# final_revision.net
KiCad netlist of a schematic drawn in EAGLE
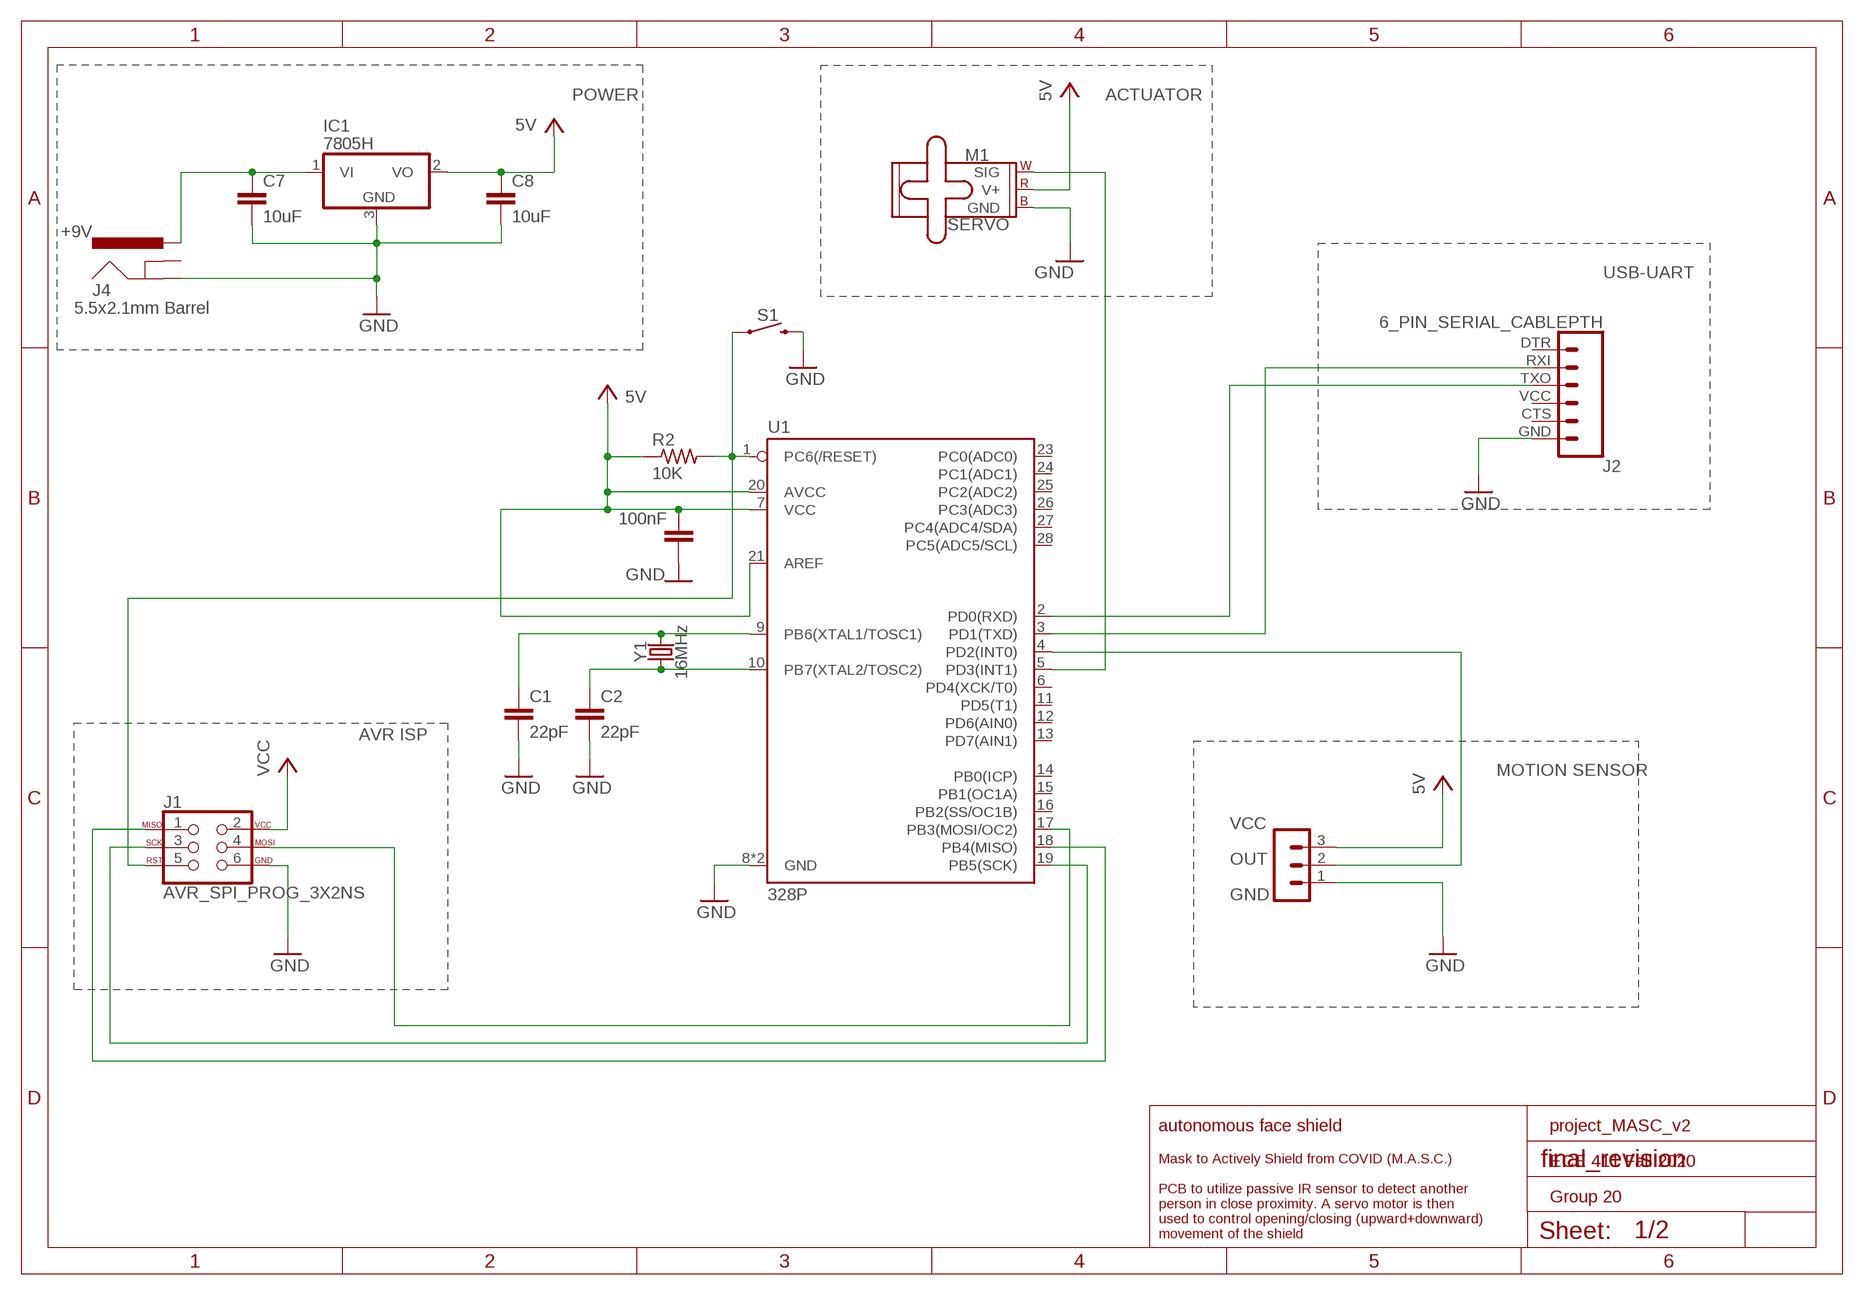
[diagram p0: schematic, sheet 1]

(export (version "E")
  (design (tool "Eeschema 10.0.6"))
  (components
    (comp (ref "C1")
      (value "22pF")
      (footprint "eagle-import:0805")
      (libsource (lib "eagle-import") (part "CAP-0805"))
    )
    (comp (ref "C2")
      (value "22pF")
      (footprint "eagle-import:0805")
      (libsource (lib "eagle-import") (part "CAP-0805"))
    )
    (comp (ref "C3")
      (value "100nF")
      (footprint "eagle-import:0805")
      (libsource (lib "eagle-import") (part "CAP-0805"))
    )
    (comp (ref "C7")
      (value "10uF")
      (footprint "eagle-import:0805")
      (libsource (lib "eagle-import") (part "CAP-0805"))
    )
    (comp (ref "C8")
      (value "10uF")
      (footprint "eagle-import:0805")
      (libsource (lib "eagle-import") (part "CAP-0805"))
    )
    (comp (ref "IC1")
      (value "7805H")
      (footprint "eagle-import:TO39")
      (libsource (lib "eagle-import") (part "78H05"))
    )
    (comp (ref "J1")
      (value "AVR_SPI_PROG_3X2NS")
      (footprint "eagle-import:2X3-NS")
      (libsource (lib "eagle-import") (part "AVR_SPI_PROG_3X2NS"))
    )
    (comp (ref "J2")
      (value "6_PIN_SERIAL_CABLEPTH")
      (footprint "eagle-import:FTDI_BASIC")
      (libsource (lib "eagle-import") (part "6_PIN_SERIAL_CABLEPTH"))
    )
    (comp (ref "J4")
      (value "5.5x2.1mm Barrel")
      (footprint "eagle-import:POWER_JACK_SMD")
      (libsource (lib "eagle-import") (part "POWER_JACKSMD"))
    )
    (comp (ref "M1")
      (value "SERVO")
      (footprint "eagle-import:1X03")
      (libsource (lib "eagle-import") (part "SERVO"))
    )
    (comp (ref "R2")
      (value "10K")
      (footprint "eagle-import:R0805")
      (libsource (lib "eagle-import") (part "R-US_R0805"))
    )
    (comp (ref "S1")
      (value "MOMENTARY-SWITCH-SPST-PTH-6.0MM")
      (footprint "eagle-import:TACTILE_SWITCH_PTH_6.0MM")
      (libsource (lib "eagle-import") (part "MOMENTARY-SWITCH-SPST-PTH-6.0MM"))
    )
    (comp (ref "SV1")
      (value "MA03-1")
      (footprint "eagle-import:MA03-1")
      (libsource (lib "eagle-import") (part "MA03-1"))
    )
    (comp (ref "U1")
      (value "328P")
      (footprint "eagle-import:DIP28")
      (libsource (lib "eagle-import") (part "ATMEGA328P_PDIP"))
    )
    (comp (ref "Y1")
      (value "16MHz")
      (footprint "eagle-import:HC49US")
      (libsource (lib "eagle-import") (part "CRYSTAL-16MHZPTH-HC49US"))
    )
  )
  (nets
    (net (code "1") (name "GND") (class "Default")
      (node (ref "C1") (pin "2") (pinfunction "2_2") (pintype "passive"))
      (node (ref "C2") (pin "2") (pinfunction "2_2") (pintype "passive"))
      (node (ref "C3") (pin "1") (pinfunction "1_1") (pintype "passive"))
      (node (ref "C7") (pin "2") (pinfunction "2_2") (pintype "passive"))
      (node (ref "C8") (pin "2") (pinfunction "2_2") (pintype "passive"))
      (node (ref "IC1") (pin "3") (pinfunction "GND_3") (pintype "passive"))
      (node (ref "J1") (pin "6") (pinfunction "6_6") (pintype "passive"))
      (node (ref "J2") (pin "GND") (pinfunction "6_GND") (pintype "passive"))
      (node (ref "J4") (pin "P$4") (pinfunction "GND_P$4") (pintype "bidirectional"))
      (node (ref "M1") (pin "3") (pinfunction "GND_3") (pintype "bidirectional"))
      (node (ref "S1") (pin "3") (pinfunction "2_3") (pintype "passive"))
      (node (ref "SV1") (pin "1") (pinfunction "1_1") (pintype "passive"))
      (node (ref "U1") (pin "22") (pinfunction "GND_22") (pintype "bidirectional"))
      (node (ref "U1") (pin "8") (pinfunction "GND_8") (pintype "bidirectional"))
    )
    (net (code "2") (name "Net-(IC1-VI)") (class "Default")
      (node (ref "C7") (pin "1") (pinfunction "1_1") (pintype "passive"))
      (node (ref "IC1") (pin "1") (pinfunction "VI_1") (pintype "input"))
      (node (ref "J4") (pin "VIN0") (pinfunction "PWR_VIN0") (pintype "bidirectional"))
    )
    (net (code "3") (name "Net-(J2-2)") (class "Default")
      (node (ref "J2") (pin "RXI") (pinfunction "2_RXI") (pintype "passive"))
      (node (ref "U1") (pin "3") (pinfunction "PD1(TXD)_3") (pintype "bidirectional"))
    )
    (net (code "4") (name "Net-(J2-3)") (class "Default")
      (node (ref "J2") (pin "TXO") (pinfunction "3_TXO") (pintype "passive"))
      (node (ref "U1") (pin "2") (pinfunction "PD0(RXD)_2") (pintype "bidirectional"))
    )
    (net (code "5") (name "Net-(M1-SIG)") (class "Default")
      (node (ref "M1") (pin "1") (pinfunction "SIG_1") (pintype "bidirectional"))
      (node (ref "U1") (pin "5") (pinfunction "PD3(INT1)_5") (pintype "bidirectional"))
    )
    (net (code "6") (name "Net-(U1-PB3(MOSI{slash}OC2))") (class "Default")
      (node (ref "J1") (pin "4") (pinfunction "4_4") (pintype "passive"))
      (node (ref "U1") (pin "17") (pinfunction "PB3(MOSI/OC2)_17") (pintype "bidirectional"))
    )
    (net (code "7") (name "Net-(U1-PB4(MISO))") (class "Default")
      (node (ref "J1") (pin "1") (pinfunction "1_1") (pintype "passive"))
      (node (ref "U1") (pin "18") (pinfunction "PB4(MISO)_18") (pintype "bidirectional"))
    )
    (net (code "8") (name "Net-(U1-PB5(SCK))") (class "Default")
      (node (ref "J1") (pin "3") (pinfunction "3_3") (pintype "passive"))
      (node (ref "U1") (pin "19") (pinfunction "PB5(SCK)_19") (pintype "bidirectional"))
    )
    (net (code "9") (name "Net-(U1-PB6(XTAL1{slash}TOSC1))") (class "Default")
      (node (ref "C1") (pin "1") (pinfunction "1_1") (pintype "passive"))
      (node (ref "U1") (pin "9") (pinfunction "PB6(XTAL1/TOSC1)_9") (pintype "bidirectional"))
      (node (ref "Y1") (pin "2") (pinfunction "2_2") (pintype "passive"))
    )
    (net (code "10") (name "Net-(U1-PB7(XTAL2{slash}TOSC2))") (class "Default")
      (node (ref "C2") (pin "1") (pinfunction "1_1") (pintype "passive"))
      (node (ref "U1") (pin "10") (pinfunction "PB7(XTAL2/TOSC2)_10") (pintype "bidirectional"))
      (node (ref "Y1") (pin "1") (pinfunction "1_1") (pintype "passive"))
    )
    (net (code "11") (name "Net-(U1-PC6({slash}RESET))") (class "Default")
      (node (ref "J1") (pin "5") (pinfunction "5_5") (pintype "passive"))
      (node (ref "R2") (pin "2") (pinfunction "2_2") (pintype "passive"))
      (node (ref "S1") (pin "1") (pinfunction "1_1") (pintype "passive"))
      (node (ref "U1") (pin "1") (pinfunction "PC6(/RESET)_1") (pintype "bidirectional"))
    )
    (net (code "12") (name "Net-(U1-PD2(INT0))") (class "Default")
      (node (ref "SV1") (pin "2") (pinfunction "2_2") (pintype "passive"))
      (node (ref "U1") (pin "4") (pinfunction "PD2(INT0)_4") (pintype "bidirectional"))
    )
    (net (code "13") (name "VCC") (class "Default")
      (node (ref "C3") (pin "2") (pinfunction "2_2") (pintype "passive"))
      (node (ref "C8") (pin "1") (pinfunction "1_1") (pintype "passive"))
      (node (ref "IC1") (pin "2") (pinfunction "VO_2") (pintype "passive"))
      (node (ref "J1") (pin "2") (pinfunction "2_2") (pintype "passive"))
      (node (ref "M1") (pin "2") (pinfunction "V+_2") (pintype "bidirectional"))
      (node (ref "R2") (pin "1") (pinfunction "1_1") (pintype "passive"))
      (node (ref "SV1") (pin "3") (pinfunction "3_3") (pintype "passive"))
      (node (ref "U1") (pin "20") (pinfunction "AVCC_20") (pintype "bidirectional"))
      (node (ref "U1") (pin "21") (pinfunction "AREF_21") (pintype "bidirectional"))
      (node (ref "U1") (pin "7") (pinfunction "VCC_7") (pintype "bidirectional"))
    )
    (net (code "14") (name "unconnected-(J2-1-PadDTR)") (class "Default")
      (node (ref "J2") (pin "DTR") (pinfunction "1_DTR") (pintype "passive"))
    )
    (net (code "15") (name "unconnected-(J2-4-PadVCC)") (class "Default")
      (node (ref "J2") (pin "VCC") (pinfunction "4_VCC") (pintype "passive"))
    )
    (net (code "16") (name "unconnected-(J2-5-PadCTS)") (class "Default")
      (node (ref "J2") (pin "CTS") (pinfunction "5_CTS") (pintype "passive"))
    )
    (net (code "17") (name "unconnected-(J4-GNDBREAK-PadGND)") (class "Default")
      (node (ref "J4") (pin "GND") (pinfunction "GNDBREAK_GND") (pintype "bidirectional"))
    )
    (net (code "18") (name "unconnected-(U1-PB0(ICP)-Pad14)") (class "Default")
      (node (ref "U1") (pin "14") (pinfunction "PB0(ICP)_14") (pintype "bidirectional"))
    )
    (net (code "19") (name "unconnected-(U1-PB1(OC1A)-Pad15)") (class "Default")
      (node (ref "U1") (pin "15") (pinfunction "PB1(OC1A)_15") (pintype "bidirectional"))
    )
    (net (code "20") (name "unconnected-(U1-PB2(SS{slash}OC1B)-Pad16)") (class "Default")
      (node (ref "U1") (pin "16") (pinfunction "PB2(SS/OC1B)_16") (pintype "bidirectional"))
    )
    (net (code "21") (name "unconnected-(U1-PC0(ADC0)-Pad23)") (class "Default")
      (node (ref "U1") (pin "23") (pinfunction "PC0(ADC0)_23") (pintype "bidirectional"))
    )
    (net (code "22") (name "unconnected-(U1-PC1(ADC1)-Pad24)") (class "Default")
      (node (ref "U1") (pin "24") (pinfunction "PC1(ADC1)_24") (pintype "bidirectional"))
    )
    (net (code "23") (name "unconnected-(U1-PC2(ADC2)-Pad25)") (class "Default")
      (node (ref "U1") (pin "25") (pinfunction "PC2(ADC2)_25") (pintype "bidirectional"))
    )
    (net (code "24") (name "unconnected-(U1-PC3(ADC3)-Pad26)") (class "Default")
      (node (ref "U1") (pin "26") (pinfunction "PC3(ADC3)_26") (pintype "bidirectional"))
    )
    (net (code "25") (name "unconnected-(U1-PC4(ADC4{slash}SDA)-Pad27)") (class "Default")
      (node (ref "U1") (pin "27") (pinfunction "PC4(ADC4/SDA)_27") (pintype "bidirectional"))
    )
    (net (code "26") (name "unconnected-(U1-PC5(ADC5{slash}SCL)-Pad28)") (class "Default")
      (node (ref "U1") (pin "28") (pinfunction "PC5(ADC5/SCL)_28") (pintype "bidirectional"))
    )
    (net (code "27") (name "unconnected-(U1-PD4(XCK{slash}T0)-Pad6)") (class "Default")
      (node (ref "U1") (pin "6") (pinfunction "PD4(XCK/T0)_6") (pintype "bidirectional"))
    )
    (net (code "28") (name "unconnected-(U1-PD5(T1)-Pad11)") (class "Default")
      (node (ref "U1") (pin "11") (pinfunction "PD5(T1)_11") (pintype "bidirectional"))
    )
    (net (code "29") (name "unconnected-(U1-PD6(AIN0)-Pad12)") (class "Default")
      (node (ref "U1") (pin "12") (pinfunction "PD6(AIN0)_12") (pintype "bidirectional"))
    )
    (net (code "30") (name "unconnected-(U1-PD7(AIN1)-Pad13)") (class "Default")
      (node (ref "U1") (pin "13") (pinfunction "PD7(AIN1)_13") (pintype "bidirectional"))
    )
  )
)
